# uC.net
KiCad netlist of a schematic drawn in Altium Designer
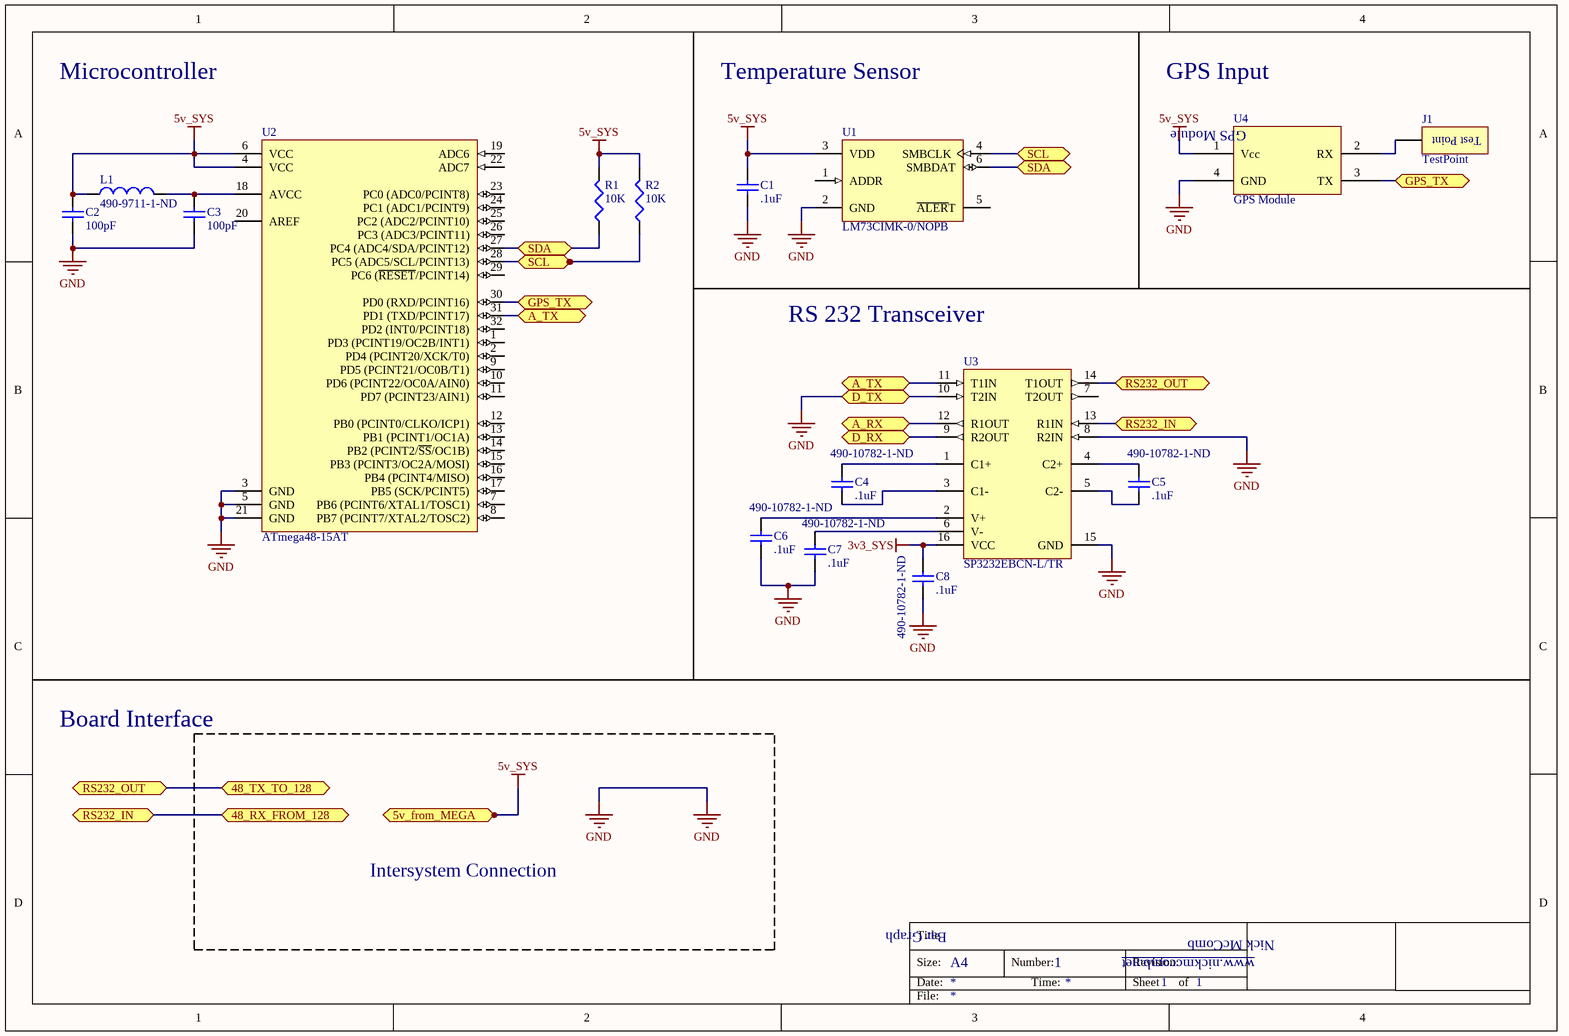
[diagram p0: uC.SchDoc]

(export (version "E")
  (design (tool "Eeschema 10.0.6"))
  (components
    (comp (ref "C1")
      (value ".1uF")
      (footprint "C0805")
      (description "Capacitor")
      (fields (field (name "Comment") "0805 style, by default") (field (name "PUBLISHER") "Altium Limited"))
      (libsource (lib "mega48") (part "Cap"))
    )
    (comp (ref "C2")
      (value "100pF")
      (footprint "C0805")
      (description "Capacitor")
      (fields (field (name "Comment") "0805 style, by default") (field (name "PUBLISHER") "Altium Limited"))
      (libsource (lib "mega48") (part "Cap"))
    )
    (comp (ref "C3")
      (value "100pF")
      (footprint "C0805")
      (description "Capacitor")
      (fields (field (name "Comment") "0805 style, by default") (field (name "PUBLISHER") "Altium Limited"))
      (libsource (lib "mega48") (part "Cap"))
    )
    (comp (ref "C4")
      (value ".1uF")
      (footprint "C0805")
      (description "Capacitor")
      (fields
        (field (name "SUPPLIER PART NUMBER 1") "490-10782-1-ND")
        (field (name "MANUFACTURER") "Murata Electronics North America")
        (field (name "MANUFACTURER PART NUMBER") "GRM21BR71H104JA01L")
        (field (name "PUBLISHER") "Altium Limited")
      )
      (libsource (lib "MultiAdapterLib") (part "Cap"))
    )
    (comp (ref "C5")
      (value ".1uF")
      (footprint "C0805")
      (description "Capacitor")
      (fields
        (field (name "SUPPLIER PART NUMBER 1") "490-10782-1-ND")
        (field (name "MANUFACTURER") "Murata Electronics North America")
        (field (name "MANUFACTURER PART NUMBER") "GRM21BR71H104JA01L")
        (field (name "PUBLISHER") "Altium Limited")
      )
      (libsource (lib "MultiAdapterLib") (part "Cap"))
    )
    (comp (ref "C6")
      (value ".1uF")
      (footprint "C0805")
      (description "Capacitor")
      (fields
        (field (name "SUPPLIER PART NUMBER 1") "490-10782-1-ND")
        (field (name "MANUFACTURER") "Murata Electronics North America")
        (field (name "MANUFACTURER PART NUMBER") "GRM21BR71H104JA01L")
        (field (name "PUBLISHER") "Altium Limited")
      )
      (libsource (lib "MultiAdapterLib") (part "Cap"))
    )
    (comp (ref "C7")
      (value ".1uF")
      (footprint "C0805")
      (description "Capacitor")
      (fields
        (field (name "SUPPLIER PART NUMBER 1") "490-10782-1-ND")
        (field (name "MANUFACTURER") "Murata Electronics North America")
        (field (name "MANUFACTURER PART NUMBER") "GRM21BR71H104JA01L")
        (field (name "PUBLISHER") "Altium Limited")
      )
      (libsource (lib "MultiAdapterLib") (part "Cap"))
    )
    (comp (ref "C8")
      (value ".1uF")
      (footprint "C0805")
      (description "Capacitor")
      (fields
        (field (name "SUPPLIER PART NUMBER 1") "490-10782-1-ND")
        (field (name "MANUFACTURER") "Murata Electronics North America")
        (field (name "MANUFACTURER PART NUMBER") "GRM21BR71H104JA01L")
        (field (name "PUBLISHER") "Altium Limited")
      )
      (libsource (lib "MultiAdapterLib") (part "Cap"))
    )
    (comp (ref "J1")
      (value "TestPoint")
      (footprint "TEST POINT")
      (libsource (lib "mega48") (part "TestPoint"))
    )
    (comp (ref "L1")
      (value "~")
      (footprint "L0805")
      (description "Murata Ferrite Bead")
      (fields
        (field (name "MANUFACTURER") "Murata")
        (field (name "MANUFACTURER PART NUMBER") "BLM21RK102SN1D")
        (field (name "SUPPLIER PART NUMBER 1") "490-9711-1-ND")
      )
      (libsource (lib "mega48") (part "Ferrite Bead"))
    )
    (comp (ref "R1")
      (value "10K")
      (footprint "J1-0603")
      (description "Resistor")
      (fields (field (name "PUBLISHER") "Altium Limited"))
      (libsource (lib "mega48") (part "Res3"))
    )
    (comp (ref "R2")
      (value "10K")
      (footprint "J1-0603")
      (description "Resistor")
      (fields (field (name "PUBLISHER") "Altium Limited"))
      (libsource (lib "mega48") (part "Res3"))
    )
    (comp (ref "U1")
      (value "LM73CIMK-0/NOPB")
      (footprint "DDC0006A_M")
      (description "2.7V, 11- to 14- Bit Digital Temperature Sensor with 2-Wire Interface, 6-pin Tiny SOT23, Pb-Free")
      (fields (field (name "MANUFACTURER") "Texas Instruments"))
      (libsource (lib "Altium Content Vault") (part "SEN-TEMP-LM73CIMK-6"))
    )
    (comp (ref "U2")
      (value "ATmega48-15AT")
      (footprint "32MA_N")
      (libsource (lib "Altium Content Vault") (part "MC-8B-ATM48-SQ32"))
    )
    (comp (ref "U3")
      (value "SP3232EBCN-L/TR")
      (footprint "EXAR-NSOIC-16_N")
      (fields (field (name "MANUFACTURER") "Exar Corporation"))
      (libsource (lib "Altium Content Vault") (part "EXAR-SP3232EB-16"))
    )
    (comp (ref "U4") (value "GPS Module") (libsource (lib "mega48") (part "GPS Module")))
  )
  (nets
    (net (code "1") (name "/48_RX_FROM_128") (class "Default")
      (node (ref "U3") (pin "13") (pinfunction "R1IN_13") (pintype "input"))
    )
    (net (code "3") (name "/A_RX") (class "Default")
      (node (ref "U3") (pin "12") (pinfunction "R1OUT_12") (pintype "output"))
    )
    (net (code "4") (name "/A_TX") (class "Default")
      (node (ref "U2") (pin "31") (pinfunction "PD1_(TXD/PCINT17)_31") (pintype "bidirectional"))
      (node (ref "U3") (pin "11") (pinfunction "T1IN_11") (pintype "input"))
    )
    (net (code "5") (name "/D_RX") (class "Default")
      (node (ref "U3") (pin "9") (pinfunction "R2OUT_9") (pintype "output"))
    )
    (net (code "6") (name "/GPS_TX") (class "Default")
      (node (ref "U2") (pin "30") (pinfunction "PD0_(RXD/PCINT16)_30") (pintype "bidirectional"))
      (node (ref "U4") (pin "3") (pinfunction "TX_3") (pintype "passive"))
    )
    (net (code "7") (name "/RS232_OUT") (class "Default")
      (node (ref "U3") (pin "14") (pinfunction "T1OUT_14") (pintype "output"))
    )
    (net (code "8") (name "/SCL") (class "Default")
      (node (ref "R2") (pin "1") (pinfunction "1_1") (pintype "passive"))
      (node (ref "U1") (pin "4") (pinfunction "SMBCLK_4") (pintype "input"))
      (node (ref "U2") (pin "28") (pinfunction "PC5_(ADC5/SCL/PCINT13)_28") (pintype "bidirectional"))
    )
    (net (code "9") (name "/SDA") (class "Default")
      (node (ref "R1") (pin "1") (pinfunction "1_1") (pintype "passive"))
      (node (ref "U1") (pin "6") (pinfunction "SMBDAT_6") (pintype "bidirectional"))
      (node (ref "U2") (pin "27") (pinfunction "PC4_(ADC4/SDA/PCINT12)_27") (pintype "bidirectional"))
    )
    (net (code "10") (name "3v3_SYS") (class "Default")
      (node (ref "C8") (pin "2") (pinfunction "2_2") (pintype "passive"))
      (node (ref "U3") (pin "16") (pinfunction "VCC_16") (pintype "power_in"))
    )
    (net (code "11") (name "5v_SYS") (class "Default")
      (node (ref "C1") (pin "2") (pinfunction "2_2") (pintype "passive"))
      (node (ref "C2") (pin "2") (pinfunction "2_2") (pintype "passive"))
      (node (ref "L1") (pin "1") (pinfunction "1_1") (pintype "passive"))
      (node (ref "R1") (pin "2") (pinfunction "2_2") (pintype "passive"))
      (node (ref "R2") (pin "2") (pinfunction "2_2") (pintype "passive"))
      (node (ref "U1") (pin "3") (pinfunction "VDD_3") (pintype "power_in"))
      (node (ref "U2") (pin "4") (pinfunction "VCC_4") (pintype "power_in"))
      (node (ref "U2") (pin "6") (pinfunction "VCC_6") (pintype "power_in"))
      (node (ref "U4") (pin "1") (pinfunction "Vcc_1") (pintype "passive"))
    )
    (net (code "12") (name "GND") (class "Default")
      (node (ref "C1") (pin "1") (pinfunction "1_1") (pintype "passive"))
      (node (ref "C2") (pin "1") (pinfunction "1_1") (pintype "passive"))
      (node (ref "C3") (pin "1") (pinfunction "1_1") (pintype "passive"))
      (node (ref "C6") (pin "1") (pinfunction "1_1") (pintype "passive"))
      (node (ref "C7") (pin "1") (pinfunction "1_1") (pintype "passive"))
      (node (ref "C8") (pin "1") (pinfunction "1_1") (pintype "passive"))
      (node (ref "U1") (pin "2") (pinfunction "GND_2") (pintype "power_in"))
      (node (ref "U2") (pin "21") (pinfunction "GND_21") (pintype "power_in"))
      (node (ref "U2") (pin "3") (pinfunction "GND_3") (pintype "power_in"))
      (node (ref "U2") (pin "5") (pinfunction "GND_5") (pintype "power_in"))
      (node (ref "U3") (pin "10") (pinfunction "T2IN_10") (pintype "input"))
      (node (ref "U3") (pin "15") (pinfunction "GND_15") (pintype "power_in"))
      (node (ref "U3") (pin "8") (pinfunction "R2IN_8") (pintype "input"))
      (node (ref "U4") (pin "4") (pinfunction "GND_4") (pintype "passive"))
    )
    (net (code "13") (name "Net-(U2-AVCC)") (class "Default")
      (node (ref "C3") (pin "2") (pinfunction "2_2") (pintype "passive"))
      (node (ref "L1") (pin "2") (pinfunction "2_2") (pintype "passive"))
      (node (ref "U2") (pin "18") (pinfunction "AVCC_18") (pintype "power_in"))
    )
    (net (code "14") (name "Net-(U3-C1+)") (class "Default")
      (node (ref "C4") (pin "2") (pinfunction "2_2") (pintype "passive"))
      (node (ref "U3") (pin "1") (pinfunction "C1+_1") (pintype "passive"))
    )
    (net (code "15") (name "Net-(U3-C1-)") (class "Default")
      (node (ref "C4") (pin "1") (pinfunction "1_1") (pintype "passive"))
      (node (ref "U3") (pin "3") (pinfunction "C1-_3") (pintype "passive"))
    )
    (net (code "16") (name "Net-(U3-C2+)") (class "Default")
      (node (ref "C5") (pin "2") (pinfunction "2_2") (pintype "passive"))
      (node (ref "U3") (pin "4") (pinfunction "C2+_4") (pintype "passive"))
    )
    (net (code "17") (name "Net-(U3-C2-)") (class "Default")
      (node (ref "C5") (pin "1") (pinfunction "1_1") (pintype "passive"))
      (node (ref "U3") (pin "5") (pinfunction "C2-_5") (pintype "passive"))
    )
    (net (code "18") (name "Net-(U3-V+)") (class "Default")
      (node (ref "C6") (pin "2") (pinfunction "2_2") (pintype "passive"))
      (node (ref "U3") (pin "2") (pinfunction "V+_2") (pintype "power_in"))
    )
    (net (code "19") (name "Net-(U3-V-)") (class "Default")
      (node (ref "C7") (pin "2") (pinfunction "2_2") (pintype "passive"))
      (node (ref "U3") (pin "6") (pinfunction "V-_6") (pintype "power_in"))
    )
    (net (code "20") (name "Net-(U4-RX)") (class "Default")
      (node (ref "J1") (pin "1") (pinfunction "1_1") (pintype "passive"))
      (node (ref "U4") (pin "2") (pinfunction "RX_2") (pintype "passive"))
    )
    (net (code "21") (name "unconnected-(U1-ADDR-Pad1)") (class "Default")
      (node (ref "U1") (pin "1") (pinfunction "ADDR_1") (pintype "input"))
    )
    (net (code "22") (name "unconnected-(U1-~{ALER}T-Pad5)") (class "Default")
      (node (ref "U1") (pin "5") (pinfunction "~{ALER}T_5") (pintype "open_collector"))
    )
    (net (code "23") (name "unconnected-(U2-ADC6-Pad19)") (class "Default")
      (node (ref "U2") (pin "19") (pinfunction "ADC6_19") (pintype "input"))
    )
    (net (code "24") (name "unconnected-(U2-ADC7-Pad22)") (class "Default")
      (node (ref "U2") (pin "22") (pinfunction "ADC7_22") (pintype "input"))
    )
    (net (code "25") (name "unconnected-(U2-AREF-Pad20)") (class "Default")
      (node (ref "U2") (pin "20") (pinfunction "AREF_20") (pintype "passive"))
    )
    (net (code "26") (name "unconnected-(U2-PB0_(PCINT0{slash}CLKO{slash}ICP1)-Pad12)") (class "Default")
      (node (ref "U2") (pin "12") (pinfunction "PB0_(PCINT0/CLKO/ICP1)_12") (pintype "bidirectional"))
    )
    (net (code "27") (name "unconnected-(U2-PB1_(PCINT1{slash}OC1A)-Pad13)") (class "Default")
      (node (ref "U2") (pin "13") (pinfunction "PB1_(PCINT1/OC1A)_13") (pintype "bidirectional"))
    )
    (net (code "28") (name "unconnected-(U2-PB2_(PCINT2{slash}~{SS}{slash}OC1B)-Pad14)") (class "Default")
      (node (ref "U2") (pin "14") (pinfunction "PB2_(PCINT2/~{SS}/OC1B)_14") (pintype "bidirectional"))
    )
    (net (code "29") (name "unconnected-(U2-PB3_(PCINT3{slash}OC2A{slash}MOSI)-Pad15)") (class "Default")
      (node (ref "U2") (pin "15") (pinfunction "PB3_(PCINT3/OC2A/MOSI)_15") (pintype "bidirectional"))
    )
    (net (code "30") (name "unconnected-(U2-PB4_(PCINT4{slash}MISO)-Pad16)") (class "Default")
      (node (ref "U2") (pin "16") (pinfunction "PB4_(PCINT4/MISO)_16") (pintype "bidirectional"))
    )
    (net (code "31") (name "unconnected-(U2-PB5_(SCK{slash}PCINT5)-Pad17)") (class "Default")
      (node (ref "U2") (pin "17") (pinfunction "PB5_(SCK/PCINT5)_17") (pintype "bidirectional"))
    )
    (net (code "32") (name "unconnected-(U2-PB6_(PCINT6{slash}XTAL1{slash}TOSC1)-Pad7)") (class "Default")
      (node (ref "U2") (pin "7") (pinfunction "PB6_(PCINT6/XTAL1/TOSC1)_7") (pintype "bidirectional"))
    )
    (net (code "33") (name "unconnected-(U2-PB7_(PCINT7{slash}XTAL2{slash}TOSC2)-Pad8)") (class "Default")
      (node (ref "U2") (pin "8") (pinfunction "PB7_(PCINT7/XTAL2/TOSC2)_8") (pintype "bidirectional"))
    )
    (net (code "34") (name "unconnected-(U2-PC0_(ADC0{slash}PCINT8)-Pad23)") (class "Default")
      (node (ref "U2") (pin "23") (pinfunction "PC0_(ADC0/PCINT8)_23") (pintype "bidirectional"))
    )
    (net (code "35") (name "unconnected-(U2-PC1_(ADC1{slash}PCINT9)-Pad24)") (class "Default")
      (node (ref "U2") (pin "24") (pinfunction "PC1_(ADC1/PCINT9)_24") (pintype "bidirectional"))
    )
    (net (code "36") (name "unconnected-(U2-PC2_(ADC2{slash}PCINT10)-Pad25)") (class "Default")
      (node (ref "U2") (pin "25") (pinfunction "PC2_(ADC2/PCINT10)_25") (pintype "bidirectional"))
    )
    (net (code "37") (name "unconnected-(U2-PC3_(ADC3{slash}PCINT11)-Pad26)") (class "Default")
      (node (ref "U2") (pin "26") (pinfunction "PC3_(ADC3/PCINT11)_26") (pintype "bidirectional"))
    )
    (net (code "38") (name "unconnected-(U2-PC6_(~{RESET}{slash}PCINT14)-Pad29)") (class "Default")
      (node (ref "U2") (pin "29") (pinfunction "PC6_(~{RESET}/PCINT14)_29") (pintype "bidirectional"))
    )
    (net (code "39") (name "unconnected-(U2-PD2_(INT0{slash}PCINT18)-Pad32)") (class "Default")
      (node (ref "U2") (pin "32") (pinfunction "PD2_(INT0/PCINT18)_32") (pintype "bidirectional"))
    )
    (net (code "40") (name "unconnected-(U2-PD3_(PCINT19{slash}OC2B{slash}INT1)-Pad1)") (class "Default")
      (node (ref "U2") (pin "1") (pinfunction "PD3_(PCINT19/OC2B/INT1)_1") (pintype "bidirectional"))
    )
    (net (code "41") (name "unconnected-(U2-PD4_(PCINT20{slash}XCK{slash}T0)-Pad2)") (class "Default")
      (node (ref "U2") (pin "2") (pinfunction "PD4_(PCINT20/XCK/T0)_2") (pintype "bidirectional"))
    )
    (net (code "42") (name "unconnected-(U2-PD5_(PCINT21{slash}OC0B{slash}T1)-Pad9)") (class "Default")
      (node (ref "U2") (pin "9") (pinfunction "PD5_(PCINT21/OC0B/T1)_9") (pintype "bidirectional"))
    )
    (net (code "43") (name "unconnected-(U2-PD6_(PCINT22{slash}OC0A{slash}AIN0)-Pad10)") (class "Default")
      (node (ref "U2") (pin "10") (pinfunction "PD6_(PCINT22/OC0A/AIN0)_10") (pintype "bidirectional"))
    )
    (net (code "44") (name "unconnected-(U2-PD7_(PCINT23{slash}AIN1)-Pad11)") (class "Default")
      (node (ref "U2") (pin "11") (pinfunction "PD7_(PCINT23/AIN1)_11") (pintype "bidirectional"))
    )
    (net (code "45") (name "unconnected-(U3-T2OUT-Pad7)") (class "Default")
      (node (ref "U3") (pin "7") (pinfunction "T2OUT_7") (pintype "output"))
    )
  )
)
